# IPT-LXe_Top.net
KiCad netlist of a schematic drawn in Altium Designer
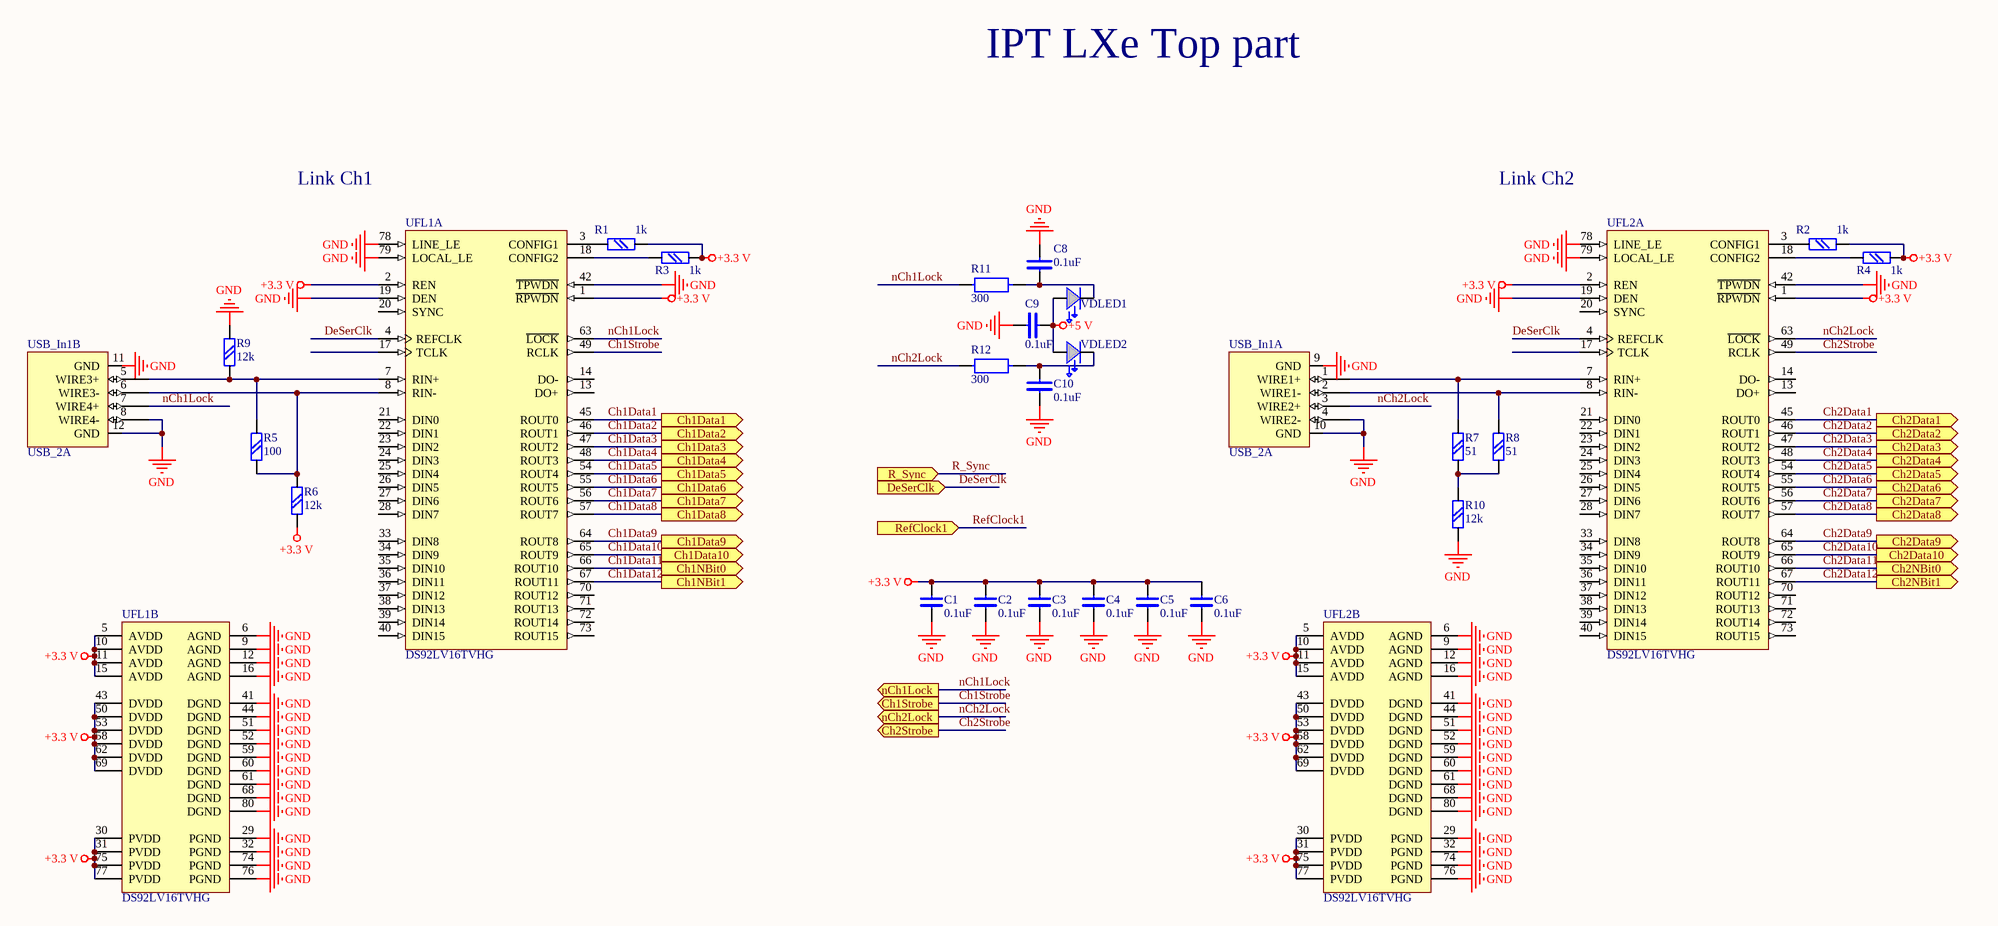
[diagram p0: IPT-LXe Top.SchDoc]

(export (version "E")
  (design (tool "Eeschema 10.0.6"))
  (components
    (comp (ref "C1") (value "0.1uF") (footprint "chip0805") (libsource (lib "") (part "C_1")))
    (comp (ref "C2") (value "0.1uF") (footprint "chip0805") (libsource (lib "") (part "C_1")))
    (comp (ref "C3") (value "0.1uF") (footprint "chip0805") (libsource (lib "") (part "C_1")))
    (comp (ref "C4") (value "0.1uF") (footprint "chip0805") (libsource (lib "") (part "C_1")))
    (comp (ref "C5") (value "0.1uF") (footprint "chip0805") (libsource (lib "") (part "C_1")))
    (comp (ref "C6") (value "0.1uF") (footprint "chip0805") (libsource (lib "") (part "C_1")))
    (comp (ref "C8") (value "0.1uF") (footprint "chip0805") (libsource (lib "*") (part "C")))
    (comp (ref "C9") (value "0.1uF") (footprint "chip0805") (libsource (lib "*") (part "C")))
    (comp (ref "C10") (value "0.1uF") (footprint "chip0805") (libsource (lib "*") (part "C")))
    (comp (ref "R1") (value "1k") (footprint "chip0805") (libsource (lib "vDevice") (part "R")))
    (comp (ref "R2") (value "1k") (footprint "chip0805") (libsource (lib "vDevice") (part "R")))
    (comp (ref "R3") (value "1k") (footprint "chip0805") (libsource (lib "vDevice") (part "R")))
    (comp (ref "R4") (value "1k") (footprint "chip0805") (libsource (lib "vDevice") (part "R")))
    (comp (ref "R5") (value "100") (footprint "chip0805") (libsource (lib "vDevice") (part "R")))
    (comp (ref "R6") (value "12k") (footprint "chip0805") (libsource (lib "vDevice") (part "R")))
    (comp (ref "R7") (value "51") (footprint "chip0805") (libsource (lib "vDevice") (part "R")))
    (comp (ref "R8") (value "51") (footprint "chip0805") (libsource (lib "vDevice") (part "R")))
    (comp (ref "R9") (value "12k") (footprint "chip0805") (libsource (lib "vDevice") (part "R")))
    (comp (ref "R10") (value "12k") (footprint "chip0805") (libsource (lib "vDevice") (part "R")))
    (comp (ref "R11") (value "300") (footprint "chip0805") (libsource (lib "") (part "R_1")))
    (comp (ref "R12") (value "300") (footprint "chip0805") (libsource (lib "") (part "R_1")))
    (comp (ref "UFL1")
      (value "DS92LV16TVHG")
      (footprint "VHG80A_N")
      (description "16-Bit Bus LVDS Serializer/Deserializer - 25 - 80 MHz, 80-pin LQFP")
      (fields
        (field (name "MANUFACTURER") "National Semiconductor")
        (field (name "PUBLISHER") "Altium Limited")
      )
      (libsource (lib "NSC Interface") (part "DS92LV16TVHG"))
    )
    (comp (ref "UFL2")
      (value "DS92LV16TVHG")
      (footprint "VHG80A_N")
      (description "16-Bit Bus LVDS Serializer/Deserializer - 25 - 80 MHz, 80-pin LQFP")
      (fields
        (field (name "MANUFACTURER") "National Semiconductor")
        (field (name "PUBLISHER") "Altium Limited")
      )
      (libsource (lib "NSC Interface") (part "DS92LV16TVHG"))
    )
    (comp (ref "USB_In1") (value "USB_2A") (footprint "USB_2A") (libsource (lib "vDevice") (part "USB_2A")))
    (comp (ref "VDLED1") (value "LED") (footprint "LED2P5_H") (libsource (lib "*") (part "AL307")))
    (comp (ref "VDLED2") (value "LED") (footprint "LED2P5_H") (libsource (lib "*") (part "AL307")))
  )
  (nets
    (net (code "1") (name "+3.3 V") (class "Default")
      (node (ref "C1") (pin "2") (pinfunction "2_2") (pintype "passive"))
      (node (ref "C2") (pin "2") (pinfunction "2_2") (pintype "passive"))
      (node (ref "C3") (pin "2") (pinfunction "2_2") (pintype "passive"))
      (node (ref "C4") (pin "2") (pinfunction "2_2") (pintype "passive"))
      (node (ref "C5") (pin "2") (pinfunction "2_2") (pintype "passive"))
      (node (ref "C6") (pin "2") (pinfunction "2_2") (pintype "passive"))
      (node (ref "R1") (pin "2") (pinfunction "2_2") (pintype "passive"))
      (node (ref "R2") (pin "2") (pinfunction "2_2") (pintype "passive"))
      (node (ref "R3") (pin "2") (pinfunction "2_2") (pintype "passive"))
      (node (ref "R4") (pin "2") (pinfunction "2_2") (pintype "passive"))
      (node (ref "R6") (pin "1") (pinfunction "1_1") (pintype "passive"))
      (node (ref "UFL1") (pin "1") (pinfunction "~{RPWDN}_1") (pintype "input"))
      (node (ref "UFL1") (pin "10") (pinfunction "AVDD_10") (pintype "power_in"))
      (node (ref "UFL1") (pin "11") (pinfunction "AVDD_11") (pintype "power_in"))
      (node (ref "UFL1") (pin "15") (pinfunction "AVDD_15") (pintype "power_in"))
      (node (ref "UFL1") (pin "2") (pinfunction "REN_2") (pintype "input"))
      (node (ref "UFL1") (pin "30") (pinfunction "PVDD_30") (pintype "power_in"))
      (node (ref "UFL1") (pin "31") (pinfunction "PVDD_31") (pintype "power_in"))
      (node (ref "UFL1") (pin "43") (pinfunction "DVDD_43") (pintype "power_in"))
      (node (ref "UFL1") (pin "5") (pinfunction "AVDD_5") (pintype "power_in"))
      (node (ref "UFL1") (pin "50") (pinfunction "DVDD_50") (pintype "power_in"))
      (node (ref "UFL1") (pin "53") (pinfunction "DVDD_53") (pintype "power_in"))
      (node (ref "UFL1") (pin "58") (pinfunction "DVDD_58") (pintype "power_in"))
      (node (ref "UFL1") (pin "62") (pinfunction "DVDD_62") (pintype "power_in"))
      (node (ref "UFL1") (pin "69") (pinfunction "DVDD_69") (pintype "power_in"))
      (node (ref "UFL1") (pin "75") (pinfunction "PVDD_75") (pintype "power_in"))
      (node (ref "UFL1") (pin "77") (pinfunction "PVDD_77") (pintype "power_in"))
      (node (ref "UFL2") (pin "1") (pinfunction "~{RPWDN}_1") (pintype "input"))
      (node (ref "UFL2") (pin "10") (pinfunction "AVDD_10") (pintype "power_in"))
      (node (ref "UFL2") (pin "11") (pinfunction "AVDD_11") (pintype "power_in"))
      (node (ref "UFL2") (pin "15") (pinfunction "AVDD_15") (pintype "power_in"))
      (node (ref "UFL2") (pin "2") (pinfunction "REN_2") (pintype "input"))
      (node (ref "UFL2") (pin "30") (pinfunction "PVDD_30") (pintype "power_in"))
      (node (ref "UFL2") (pin "31") (pinfunction "PVDD_31") (pintype "power_in"))
      (node (ref "UFL2") (pin "43") (pinfunction "DVDD_43") (pintype "power_in"))
      (node (ref "UFL2") (pin "5") (pinfunction "AVDD_5") (pintype "power_in"))
      (node (ref "UFL2") (pin "50") (pinfunction "DVDD_50") (pintype "power_in"))
      (node (ref "UFL2") (pin "53") (pinfunction "DVDD_53") (pintype "power_in"))
      (node (ref "UFL2") (pin "58") (pinfunction "DVDD_58") (pintype "power_in"))
      (node (ref "UFL2") (pin "62") (pinfunction "DVDD_62") (pintype "power_in"))
      (node (ref "UFL2") (pin "69") (pinfunction "DVDD_69") (pintype "power_in"))
      (node (ref "UFL2") (pin "75") (pinfunction "PVDD_75") (pintype "power_in"))
      (node (ref "UFL2") (pin "77") (pinfunction "PVDD_77") (pintype "power_in"))
    )
    (net (code "2") (name "+5 V") (class "Default")
      (node (ref "C9") (pin "2") (pinfunction "2_2") (pintype "passive"))
      (node (ref "VDLED1") (pin "ANOD") (pinfunction "ANOD_ANOD") (pintype "passive"))
      (node (ref "VDLED2") (pin "ANOD") (pinfunction "ANOD_ANOD") (pintype "passive"))
    )
    (net (code "3") (name "/Ch1Data1") (class "Default")
      (node (ref "UFL1") (pin "45") (pinfunction "ROUT0_45") (pintype "output"))
    )
    (net (code "4") (name "/Ch1Data2") (class "Default")
      (node (ref "UFL1") (pin "46") (pinfunction "ROUT1_46") (pintype "output"))
    )
    (net (code "5") (name "/Ch1Data3") (class "Default")
      (node (ref "UFL1") (pin "47") (pinfunction "ROUT2_47") (pintype "output"))
    )
    (net (code "6") (name "/Ch1Data4") (class "Default")
      (node (ref "UFL1") (pin "48") (pinfunction "ROUT3_48") (pintype "output"))
    )
    (net (code "7") (name "/Ch1Data5") (class "Default")
      (node (ref "UFL1") (pin "54") (pinfunction "ROUT4_54") (pintype "output"))
    )
    (net (code "8") (name "/Ch1Data6") (class "Default")
      (node (ref "UFL1") (pin "55") (pinfunction "ROUT5_55") (pintype "output"))
    )
    (net (code "9") (name "/Ch1Data7") (class "Default")
      (node (ref "UFL1") (pin "56") (pinfunction "ROUT6_56") (pintype "output"))
    )
    (net (code "10") (name "/Ch1Data8") (class "Default")
      (node (ref "UFL1") (pin "57") (pinfunction "ROUT7_57") (pintype "output"))
    )
    (net (code "11") (name "/Ch1Data9") (class "Default")
      (node (ref "UFL1") (pin "64") (pinfunction "ROUT8_64") (pintype "output"))
    )
    (net (code "12") (name "/Ch1Data10") (class "Default")
      (node (ref "UFL1") (pin "65") (pinfunction "ROUT9_65") (pintype "output"))
    )
    (net (code "13") (name "/Ch1Data11") (class "Default")
      (node (ref "UFL1") (pin "66") (pinfunction "ROUT10_66") (pintype "output"))
    )
    (net (code "14") (name "/Ch1Data12") (class "Default")
      (node (ref "UFL1") (pin "67") (pinfunction "ROUT11_67") (pintype "output"))
    )
    (net (code "15") (name "/Ch1Strobe") (class "Default")
      (node (ref "UFL1") (pin "49") (pinfunction "RCLK_49") (pintype "output"))
    )
    (net (code "16") (name "/Ch2Data1") (class "Default")
      (node (ref "UFL2") (pin "45") (pinfunction "ROUT0_45") (pintype "output"))
    )
    (net (code "17") (name "/Ch2Data2") (class "Default")
      (node (ref "UFL2") (pin "46") (pinfunction "ROUT1_46") (pintype "output"))
    )
    (net (code "18") (name "/Ch2Data3") (class "Default")
      (node (ref "UFL2") (pin "47") (pinfunction "ROUT2_47") (pintype "output"))
    )
    (net (code "19") (name "/Ch2Data4") (class "Default")
      (node (ref "UFL2") (pin "48") (pinfunction "ROUT3_48") (pintype "output"))
    )
    (net (code "20") (name "/Ch2Data5") (class "Default")
      (node (ref "UFL2") (pin "54") (pinfunction "ROUT4_54") (pintype "output"))
    )
    (net (code "21") (name "/Ch2Data6") (class "Default")
      (node (ref "UFL2") (pin "55") (pinfunction "ROUT5_55") (pintype "output"))
    )
    (net (code "22") (name "/Ch2Data7") (class "Default")
      (node (ref "UFL2") (pin "56") (pinfunction "ROUT6_56") (pintype "output"))
    )
    (net (code "23") (name "/Ch2Data8") (class "Default")
      (node (ref "UFL2") (pin "57") (pinfunction "ROUT7_57") (pintype "output"))
    )
    (net (code "24") (name "/Ch2Data9") (class "Default")
      (node (ref "UFL2") (pin "64") (pinfunction "ROUT8_64") (pintype "output"))
    )
    (net (code "25") (name "/Ch2Data10") (class "Default")
      (node (ref "UFL2") (pin "65") (pinfunction "ROUT9_65") (pintype "output"))
    )
    (net (code "26") (name "/Ch2Data11") (class "Default")
      (node (ref "UFL2") (pin "66") (pinfunction "ROUT10_66") (pintype "output"))
    )
    (net (code "27") (name "/Ch2Data12") (class "Default")
      (node (ref "UFL2") (pin "67") (pinfunction "ROUT11_67") (pintype "output"))
    )
    (net (code "28") (name "/Ch2Strobe") (class "Default")
      (node (ref "UFL2") (pin "49") (pinfunction "RCLK_49") (pintype "output"))
    )
    (net (code "29") (name "/DeSerClk") (class "Default")
      (node (ref "UFL1") (pin "4") (pinfunction "REFCLK_4") (pintype "input"))
      (node (ref "UFL2") (pin "4") (pinfunction "REFCLK_4") (pintype "input"))
    )
    (net (code "32") (name "/nCh1Lock") (class "Default")
      (node (ref "R11") (pin "1") (pinfunction "1_1") (pintype "passive"))
      (node (ref "UFL1") (pin "63") (pinfunction "~{LOCK}_63") (pintype "output"))
      (node (ref "USB_In1") (pin "7") (pinfunction "WIRE4+_7") (pintype "bidirectional"))
    )
    (net (code "33") (name "/nCh2Lock") (class "Default")
      (node (ref "R12") (pin "1") (pinfunction "1_1") (pintype "passive"))
      (node (ref "UFL2") (pin "63") (pinfunction "~{LOCK}_63") (pintype "output"))
      (node (ref "USB_In1") (pin "3") (pinfunction "WIRE2+_3") (pintype "bidirectional"))
    )
    (net (code "34") (name "GND") (class "Default")
      (node (ref "C1") (pin "1") (pinfunction "1_1") (pintype "passive"))
      (node (ref "C10") (pin "2") (pinfunction "2_2") (pintype "passive"))
      (node (ref "C2") (pin "1") (pinfunction "1_1") (pintype "passive"))
      (node (ref "C3") (pin "1") (pinfunction "1_1") (pintype "passive"))
      (node (ref "C4") (pin "1") (pinfunction "1_1") (pintype "passive"))
      (node (ref "C5") (pin "1") (pinfunction "1_1") (pintype "passive"))
      (node (ref "C6") (pin "1") (pinfunction "1_1") (pintype "passive"))
      (node (ref "C8") (pin "1") (pinfunction "1_1") (pintype "passive"))
      (node (ref "C9") (pin "1") (pinfunction "1_1") (pintype "passive"))
      (node (ref "R10") (pin "1") (pinfunction "1_1") (pintype "passive"))
      (node (ref "R9") (pin "1") (pinfunction "1_1") (pintype "passive"))
      (node (ref "UFL1") (pin "12") (pinfunction "AGND_12") (pintype "power_in"))
      (node (ref "UFL1") (pin "16") (pinfunction "AGND_16") (pintype "power_in"))
      (node (ref "UFL1") (pin "19") (pinfunction "DEN_19") (pintype "input"))
      (node (ref "UFL1") (pin "29") (pinfunction "PGND_29") (pintype "power_in"))
      (node (ref "UFL1") (pin "32") (pinfunction "PGND_32") (pintype "power_in"))
      (node (ref "UFL1") (pin "41") (pinfunction "DGND_41") (pintype "power_in"))
      (node (ref "UFL1") (pin "42") (pinfunction "~{TPWDN}_42") (pintype "input"))
      (node (ref "UFL1") (pin "44") (pinfunction "DGND_44") (pintype "power_in"))
      (node (ref "UFL1") (pin "51") (pinfunction "DGND_51") (pintype "power_in"))
      (node (ref "UFL1") (pin "52") (pinfunction "DGND_52") (pintype "power_in"))
      (node (ref "UFL1") (pin "59") (pinfunction "DGND_59") (pintype "power_in"))
      (node (ref "UFL1") (pin "6") (pinfunction "AGND_6") (pintype "power_in"))
      (node (ref "UFL1") (pin "60") (pinfunction "DGND_60") (pintype "power_in"))
      (node (ref "UFL1") (pin "61") (pinfunction "DGND_61") (pintype "power_in"))
      (node (ref "UFL1") (pin "68") (pinfunction "DGND_68") (pintype "power_in"))
      (node (ref "UFL1") (pin "74") (pinfunction "PGND_74") (pintype "power_in"))
      (node (ref "UFL1") (pin "76") (pinfunction "PGND_76") (pintype "power_in"))
      (node (ref "UFL1") (pin "78") (pinfunction "LINE_LE_78") (pintype "input"))
      (node (ref "UFL1") (pin "79") (pinfunction "LOCAL_LE_79") (pintype "input"))
      (node (ref "UFL1") (pin "80") (pinfunction "DGND_80") (pintype "power_in"))
      (node (ref "UFL1") (pin "9") (pinfunction "AGND_9") (pintype "power_in"))
      (node (ref "UFL2") (pin "12") (pinfunction "AGND_12") (pintype "power_in"))
      (node (ref "UFL2") (pin "16") (pinfunction "AGND_16") (pintype "power_in"))
      (node (ref "UFL2") (pin "19") (pinfunction "DEN_19") (pintype "input"))
      (node (ref "UFL2") (pin "29") (pinfunction "PGND_29") (pintype "power_in"))
      (node (ref "UFL2") (pin "32") (pinfunction "PGND_32") (pintype "power_in"))
      (node (ref "UFL2") (pin "41") (pinfunction "DGND_41") (pintype "power_in"))
      (node (ref "UFL2") (pin "42") (pinfunction "~{TPWDN}_42") (pintype "input"))
      (node (ref "UFL2") (pin "44") (pinfunction "DGND_44") (pintype "power_in"))
      (node (ref "UFL2") (pin "51") (pinfunction "DGND_51") (pintype "power_in"))
      (node (ref "UFL2") (pin "52") (pinfunction "DGND_52") (pintype "power_in"))
      (node (ref "UFL2") (pin "59") (pinfunction "DGND_59") (pintype "power_in"))
      (node (ref "UFL2") (pin "6") (pinfunction "AGND_6") (pintype "power_in"))
      (node (ref "UFL2") (pin "60") (pinfunction "DGND_60") (pintype "power_in"))
      (node (ref "UFL2") (pin "61") (pinfunction "DGND_61") (pintype "power_in"))
      (node (ref "UFL2") (pin "68") (pinfunction "DGND_68") (pintype "power_in"))
      (node (ref "UFL2") (pin "74") (pinfunction "PGND_74") (pintype "power_in"))
      (node (ref "UFL2") (pin "76") (pinfunction "PGND_76") (pintype "power_in"))
      (node (ref "UFL2") (pin "78") (pinfunction "LINE_LE_78") (pintype "input"))
      (node (ref "UFL2") (pin "79") (pinfunction "LOCAL_LE_79") (pintype "input"))
      (node (ref "UFL2") (pin "80") (pinfunction "DGND_80") (pintype "power_in"))
      (node (ref "UFL2") (pin "9") (pinfunction "AGND_9") (pintype "power_in"))
      (node (ref "USB_In1") (pin "10") (pinfunction "GND_10") (pintype "passive"))
      (node (ref "USB_In1") (pin "11") (pinfunction "GND_11") (pintype "passive"))
      (node (ref "USB_In1") (pin "12") (pinfunction "GND_12") (pintype "passive"))
      (node (ref "USB_In1") (pin "4") (pinfunction "WIRE2-_4") (pintype "bidirectional"))
      (node (ref "USB_In1") (pin "8") (pinfunction "WIRE4-_8") (pintype "bidirectional"))
      (node (ref "USB_In1") (pin "9") (pinfunction "GND_9") (pintype "passive"))
    )
    (net (code "35") (name "Net-(C8-Pad2)") (class "Default")
      (node (ref "C8") (pin "2") (pinfunction "2_2") (pintype "passive"))
      (node (ref "R11") (pin "2") (pinfunction "2_2") (pintype "passive"))
      (node (ref "VDLED1") (pin "CATH") (pinfunction "CATH_CATH") (pintype "passive"))
    )
    (net (code "36") (name "Net-(C10-Pad1)") (class "Default")
      (node (ref "C10") (pin "1") (pinfunction "1_1") (pintype "passive"))
      (node (ref "R12") (pin "2") (pinfunction "2_2") (pintype "passive"))
      (node (ref "VDLED2") (pin "CATH") (pinfunction "CATH_CATH") (pintype "passive"))
    )
    (net (code "37") (name "Net-(R10-Pad2)") (class "Default")
      (node (ref "R10") (pin "2") (pinfunction "2_2") (pintype "passive"))
      (node (ref "R7") (pin "1") (pinfunction "1_1") (pintype "passive"))
      (node (ref "R8") (pin "1") (pinfunction "1_1") (pintype "passive"))
    )
    (net (code "38") (name "Net-(UFL1A-CONFIG1)") (class "Default")
      (node (ref "R1") (pin "1") (pinfunction "1_1") (pintype "passive"))
      (node (ref "UFL1") (pin "3") (pinfunction "CONFIG1_3") (pintype "passive"))
    )
    (net (code "39") (name "Net-(UFL1A-CONFIG2)") (class "Default")
      (node (ref "R3") (pin "1") (pinfunction "1_1") (pintype "passive"))
      (node (ref "UFL1") (pin "18") (pinfunction "CONFIG2_18") (pintype "passive"))
    )
    (net (code "40") (name "Net-(UFL1A-RIN+)") (class "Default")
      (node (ref "R5") (pin "2") (pinfunction "2_2") (pintype "passive"))
      (node (ref "R9") (pin "2") (pinfunction "2_2") (pintype "passive"))
      (node (ref "UFL1") (pin "7") (pinfunction "RIN+_7") (pintype "input"))
      (node (ref "USB_In1") (pin "5") (pinfunction "WIRE3+_5") (pintype "bidirectional"))
    )
    (net (code "41") (name "Net-(UFL1A-RIN-)") (class "Default")
      (node (ref "R5") (pin "1") (pinfunction "1_1") (pintype "passive"))
      (node (ref "R6") (pin "2") (pinfunction "2_2") (pintype "passive"))
      (node (ref "UFL1") (pin "8") (pinfunction "RIN-_8") (pintype "input"))
      (node (ref "USB_In1") (pin "6") (pinfunction "WIRE3-_6") (pintype "bidirectional"))
    )
    (net (code "42") (name "Net-(UFL2A-CONFIG1)") (class "Default")
      (node (ref "R2") (pin "1") (pinfunction "1_1") (pintype "passive"))
      (node (ref "UFL2") (pin "3") (pinfunction "CONFIG1_3") (pintype "passive"))
    )
    (net (code "43") (name "Net-(UFL2A-CONFIG2)") (class "Default")
      (node (ref "R4") (pin "1") (pinfunction "1_1") (pintype "passive"))
      (node (ref "UFL2") (pin "18") (pinfunction "CONFIG2_18") (pintype "passive"))
    )
    (net (code "44") (name "Net-(UFL2A-RIN+)") (class "Default")
      (node (ref "R7") (pin "2") (pinfunction "2_2") (pintype "passive"))
      (node (ref "UFL2") (pin "7") (pinfunction "RIN+_7") (pintype "input"))
      (node (ref "USB_In1") (pin "1") (pinfunction "WIRE1+_1") (pintype "bidirectional"))
    )
    (net (code "45") (name "Net-(UFL2A-RIN-)") (class "Default")
      (node (ref "R8") (pin "2") (pinfunction "2_2") (pintype "passive"))
      (node (ref "UFL2") (pin "8") (pinfunction "RIN-_8") (pintype "input"))
      (node (ref "USB_In1") (pin "2") (pinfunction "WIRE1-_2") (pintype "bidirectional"))
    )
    (net (code "46") (name "unconnected-(UFL1A-DIN0-Pad21)") (class "Default")
      (node (ref "UFL1") (pin "21") (pinfunction "DIN0_21") (pintype "input"))
    )
    (net (code "47") (name "unconnected-(UFL1A-DIN1-Pad22)") (class "Default")
      (node (ref "UFL1") (pin "22") (pinfunction "DIN1_22") (pintype "input"))
    )
    (net (code "48") (name "unconnected-(UFL1A-DIN2-Pad23)") (class "Default")
      (node (ref "UFL1") (pin "23") (pinfunction "DIN2_23") (pintype "input"))
    )
    (net (code "49") (name "unconnected-(UFL1A-DIN3-Pad24)") (class "Default")
      (node (ref "UFL1") (pin "24") (pinfunction "DIN3_24") (pintype "input"))
    )
    (net (code "50") (name "unconnected-(UFL1A-DIN4-Pad25)") (class "Default")
      (node (ref "UFL1") (pin "25") (pinfunction "DIN4_25") (pintype "input"))
    )
    (net (code "51") (name "unconnected-(UFL1A-DIN5-Pad26)") (class "Default")
      (node (ref "UFL1") (pin "26") (pinfunction "DIN5_26") (pintype "input"))
    )
    (net (code "52") (name "unconnected-(UFL1A-DIN6-Pad27)") (class "Default")
      (node (ref "UFL1") (pin "27") (pinfunction "DIN6_27") (pintype "input"))
    )
    (net (code "53") (name "unconnected-(UFL1A-DIN7-Pad28)") (class "Default")
      (node (ref "UFL1") (pin "28") (pinfunction "DIN7_28") (pintype "input"))
    )
    (net (code "54") (name "unconnected-(UFL1A-DIN8-Pad33)") (class "Default")
      (node (ref "UFL1") (pin "33") (pinfunction "DIN8_33") (pintype "input"))
    )
    (net (code "55") (name "unconnected-(UFL1A-DIN9-Pad34)") (class "Default")
      (node (ref "UFL1") (pin "34") (pinfunction "DIN9_34") (pintype "input"))
    )
    (net (code "56") (name "unconnected-(UFL1A-DIN10-Pad35)") (class "Default")
      (node (ref "UFL1") (pin "35") (pinfunction "DIN10_35") (pintype "input"))
    )
    (net (code "57") (name "unconnected-(UFL1A-DIN11-Pad36)") (class "Default")
      (node (ref "UFL1") (pin "36") (pinfunction "DIN11_36") (pintype "input"))
    )
    (net (code "58") (name "unconnected-(UFL1A-DIN12-Pad37)") (class "Default")
      (node (ref "UFL1") (pin "37") (pinfunction "DIN12_37") (pintype "input"))
    )
    (net (code "59") (name "unconnected-(UFL1A-DIN13-Pad38)") (class "Default")
      (node (ref "UFL1") (pin "38") (pinfunction "DIN13_38") (pintype "input"))
    )
    (net (code "60") (name "unconnected-(UFL1A-DIN14-Pad39)") (class "Default")
      (node (ref "UFL1") (pin "39") (pinfunction "DIN14_39") (pintype "input"))
    )
    (net (code "61") (name "unconnected-(UFL1A-DIN15-Pad40)") (class "Default")
      (node (ref "UFL1") (pin "40") (pinfunction "DIN15_40") (pintype "input"))
    )
    (net (code "62") (name "unconnected-(UFL1A-DO+-Pad13)") (class "Default")
      (node (ref "UFL1") (pin "13") (pinfunction "DO+_13") (pintype "output"))
    )
    (net (code "63") (name "unconnected-(UFL1A-DO--Pad14)") (class "Default")
      (node (ref "UFL1") (pin "14") (pinfunction "DO-_14") (pintype "output"))
    )
    (net (code "64") (name "unconnected-(UFL1A-ROUT12-Pad70)") (class "Default")
      (node (ref "UFL1") (pin "70") (pinfunction "ROUT12_70") (pintype "output"))
    )
    (net (code "65") (name "unconnected-(UFL1A-ROUT13-Pad71)") (class "Default")
      (node (ref "UFL1") (pin "71") (pinfunction "ROUT13_71") (pintype "output"))
    )
    (net (code "66") (name "unconnected-(UFL1A-ROUT14-Pad72)") (class "Default")
      (node (ref "UFL1") (pin "72") (pinfunction "ROUT14_72") (pintype "output"))
    )
    (net (code "67") (name "unconnected-(UFL1A-ROUT15-Pad73)") (class "Default")
      (node (ref "UFL1") (pin "73") (pinfunction "ROUT15_73") (pintype "output"))
    )
    (net (code "68") (name "unconnected-(UFL1A-SYNC-Pad20)") (class "Default")
      (node (ref "UFL1") (pin "20") (pinfunction "SYNC_20") (pintype "input"))
    )
    (net (code "69") (name "unconnected-(UFL1A-TCLK-Pad17)") (class "Default")
      (node (ref "UFL1") (pin "17") (pinfunction "TCLK_17") (pintype "input"))
    )
    (net (code "70") (name "unconnected-(UFL2A-DIN0-Pad21)") (class "Default")
      (node (ref "UFL2") (pin "21") (pinfunction "DIN0_21") (pintype "input"))
    )
    (net (code "71") (name "unconnected-(UFL2A-DIN1-Pad22)") (class "Default")
      (node (ref "UFL2") (pin "22") (pinfunction "DIN1_22") (pintype "input"))
    )
    (net (code "72") (name "unconnected-(UFL2A-DIN2-Pad23)") (class "Default")
      (node (ref "UFL2") (pin "23") (pinfunction "DIN2_23") (pintype "input"))
    )
    (net (code "73") (name "unconnected-(UFL2A-DIN3-Pad24)") (class "Default")
      (node (ref "UFL2") (pin "24") (pinfunction "DIN3_24") (pintype "input"))
    )
    (net (code "74") (name "unconnected-(UFL2A-DIN4-Pad25)") (class "Default")
      (node (ref "UFL2") (pin "25") (pinfunction "DIN4_25") (pintype "input"))
    )
    (net (code "75") (name "unconnected-(UFL2A-DIN5-Pad26)") (class "Default")
      (node (ref "UFL2") (pin "26") (pinfunction "DIN5_26") (pintype "input"))
    )
    (net (code "76") (name "unconnected-(UFL2A-DIN6-Pad27)") (class "Default")
      (node (ref "UFL2") (pin "27") (pinfunction "DIN6_27") (pintype "input"))
    )
    (net (code "77") (name "unconnected-(UFL2A-DIN7-Pad28)") (class "Default")
      (node (ref "UFL2") (pin "28") (pinfunction "DIN7_28") (pintype "input"))
    )
    (net (code "78") (name "unconnected-(UFL2A-DIN8-Pad33)") (class "Default")
      (node (ref "UFL2") (pin "33") (pinfunction "DIN8_33") (pintype "input"))
    )
    (net (code "79") (name "unconnected-(UFL2A-DIN9-Pad34)") (class "Default")
      (node (ref "UFL2") (pin "34") (pinfunction "DIN9_34") (pintype "input"))
    )
    (net (code "80") (name "unconnected-(UFL2A-DIN10-Pad35)") (class "Default")
      (node (ref "UFL2") (pin "35") (pinfunction "DIN10_35") (pintype "input"))
    )
    (net (code "81") (name "unconnected-(UFL2A-DIN11-Pad36)") (class "Default")
      (node (ref "UFL2") (pin "36") (pinfunction "DIN11_36") (pintype "input"))
    )
    (net (code "82") (name "unconnected-(UFL2A-DIN12-Pad37)") (class "Default")
      (node (ref "UFL2") (pin "37") (pinfunction "DIN12_37") (pintype "input"))
    )
    (net (code "83") (name "unconnected-(UFL2A-DIN13-Pad38)") (class "Default")
      (node (ref "UFL2") (pin "38") (pinfunction "DIN13_38") (pintype "input"))
    )
    (net (code "84") (name "unconnected-(UFL2A-DIN14-Pad39)") (class "Default")
      (node (ref "UFL2") (pin "39") (pinfunction "DIN14_39") (pintype "input"))
    )
    (net (code "85") (name "unconnected-(UFL2A-DIN15-Pad40)") (class "Default")
      (node (ref "UFL2") (pin "40") (pinfunction "DIN15_40") (pintype "input"))
    )
    (net (code "86") (name "unconnected-(UFL2A-DO+-Pad13)") (class "Default")
      (node (ref "UFL2") (pin "13") (pinfunction "DO+_13") (pintype "output"))
    )
    (net (code "87") (name "unconnected-(UFL2A-DO--Pad14)") (class "Default")
      (node (ref "UFL2") (pin "14") (pinfunction "DO-_14") (pintype "output"))
    )
    (net (code "88") (name "unconnected-(UFL2A-ROUT12-Pad70)") (class "Default")
      (node (ref "UFL2") (pin "70") (pinfunction "ROUT12_70") (pintype "output"))
    )
    (net (code "89") (name "unconnected-(UFL2A-ROUT13-Pad71)") (class "Default")
      (node (ref "UFL2") (pin "71") (pinfunction "ROUT13_71") (pintype "output"))
    )
    (net (code "90") (name "unconnected-(UFL2A-ROUT14-Pad72)") (class "Default")
      (node (ref "UFL2") (pin "72") (pinfunction "ROUT14_72") (pintype "output"))
    )
    (net (code "91") (name "unconnected-(UFL2A-ROUT15-Pad73)") (class "Default")
      (node (ref "UFL2") (pin "73") (pinfunction "ROUT15_73") (pintype "output"))
    )
    (net (code "92") (name "unconnected-(UFL2A-SYNC-Pad20)") (class "Default")
      (node (ref "UFL2") (pin "20") (pinfunction "SYNC_20") (pintype "input"))
    )
    (net (code "93") (name "unconnected-(UFL2A-TCLK-Pad17)") (class "Default")
      (node (ref "UFL2") (pin "17") (pinfunction "TCLK_17") (pintype "input"))
    )
  )
)
